# CharlieReactorBreakout.net
KiCad netlist of a schematic drawn in EAGLE
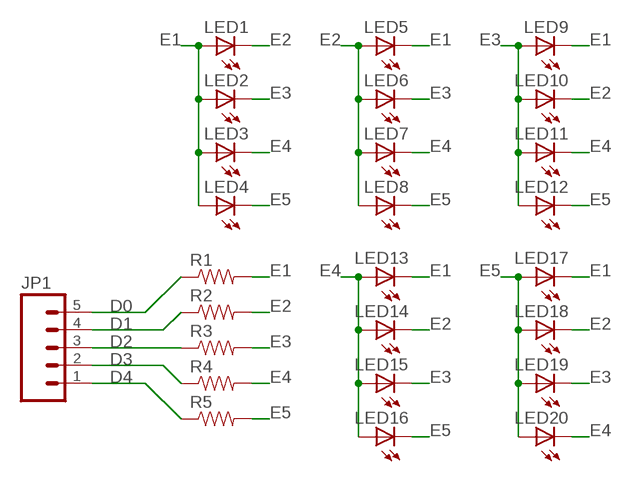
[diagram p0: schematic, sheet 1]

(export (version "E")
  (design (tool "Eeschema 10.0.6"))
  (components
    (comp (ref "JP1")
      (value "M05PTH")
      (footprint "eagle-import:1X05")
      (libsource (lib "eagle-import") (part "M05PTH"))
    )
    (comp (ref "LED1")
      (value "LEDOVAL")
      (footprint "eagle-import:LED-OVAL")
      (libsource (lib "eagle-import") (part "LEDOVAL"))
    )
    (comp (ref "LED2")
      (value "LEDOVAL")
      (footprint "eagle-import:LED-OVAL")
      (libsource (lib "eagle-import") (part "LEDOVAL"))
    )
    (comp (ref "LED3")
      (value "LEDOVAL")
      (footprint "eagle-import:LED-OVAL")
      (libsource (lib "eagle-import") (part "LEDOVAL"))
    )
    (comp (ref "LED4")
      (value "LEDOVAL")
      (footprint "eagle-import:LED-OVAL")
      (libsource (lib "eagle-import") (part "LEDOVAL"))
    )
    (comp (ref "LED5")
      (value "LEDOVAL")
      (footprint "eagle-import:LED-OVAL")
      (libsource (lib "eagle-import") (part "LEDOVAL"))
    )
    (comp (ref "LED6")
      (value "LEDOVAL")
      (footprint "eagle-import:LED-OVAL")
      (libsource (lib "eagle-import") (part "LEDOVAL"))
    )
    (comp (ref "LED7")
      (value "LEDOVAL")
      (footprint "eagle-import:LED-OVAL")
      (libsource (lib "eagle-import") (part "LEDOVAL"))
    )
    (comp (ref "LED8")
      (value "LEDOVAL")
      (footprint "eagle-import:LED-OVAL")
      (libsource (lib "eagle-import") (part "LEDOVAL"))
    )
    (comp (ref "LED9")
      (value "LEDOVAL")
      (footprint "eagle-import:LED-OVAL")
      (libsource (lib "eagle-import") (part "LEDOVAL"))
    )
    (comp (ref "LED10")
      (value "LEDOVAL")
      (footprint "eagle-import:LED-OVAL")
      (libsource (lib "eagle-import") (part "LEDOVAL"))
    )
    (comp (ref "LED11")
      (value "LEDOVAL")
      (footprint "eagle-import:LED-OVAL")
      (libsource (lib "eagle-import") (part "LEDOVAL"))
    )
    (comp (ref "LED12")
      (value "LEDOVAL")
      (footprint "eagle-import:LED-OVAL")
      (libsource (lib "eagle-import") (part "LEDOVAL"))
    )
    (comp (ref "LED13")
      (value "LEDOVAL")
      (footprint "eagle-import:LED-OVAL")
      (libsource (lib "eagle-import") (part "LEDOVAL"))
    )
    (comp (ref "LED14")
      (value "LEDOVAL")
      (footprint "eagle-import:LED-OVAL")
      (libsource (lib "eagle-import") (part "LEDOVAL"))
    )
    (comp (ref "LED15")
      (value "LEDOVAL")
      (footprint "eagle-import:LED-OVAL")
      (libsource (lib "eagle-import") (part "LEDOVAL"))
    )
    (comp (ref "LED16")
      (value "LEDOVAL")
      (footprint "eagle-import:LED-OVAL")
      (libsource (lib "eagle-import") (part "LEDOVAL"))
    )
    (comp (ref "LED17")
      (value "LEDOVAL")
      (footprint "eagle-import:LED-OVAL")
      (libsource (lib "eagle-import") (part "LEDOVAL"))
    )
    (comp (ref "LED18")
      (value "LEDOVAL")
      (footprint "eagle-import:LED-OVAL")
      (libsource (lib "eagle-import") (part "LEDOVAL"))
    )
    (comp (ref "LED19")
      (value "LEDOVAL")
      (footprint "eagle-import:LED-OVAL")
      (libsource (lib "eagle-import") (part "LEDOVAL"))
    )
    (comp (ref "LED20")
      (value "LEDOVAL")
      (footprint "eagle-import:LED-OVAL")
      (libsource (lib "eagle-import") (part "LEDOVAL"))
    )
    (comp (ref "R1")
      (value "RESISTORAXIAL-0.3")
      (footprint "eagle-import:AXIAL-0.3")
      (libsource (lib "eagle-import") (part "RESISTORAXIAL-0.3"))
    )
    (comp (ref "R2")
      (value "RESISTORAXIAL-0.3")
      (footprint "eagle-import:AXIAL-0.3")
      (libsource (lib "eagle-import") (part "RESISTORAXIAL-0.3"))
    )
    (comp (ref "R3")
      (value "RESISTORAXIAL-0.3")
      (footprint "eagle-import:AXIAL-0.3")
      (libsource (lib "eagle-import") (part "RESISTORAXIAL-0.3"))
    )
    (comp (ref "R4")
      (value "RESISTORAXIAL-0.3")
      (footprint "eagle-import:AXIAL-0.3")
      (libsource (lib "eagle-import") (part "RESISTORAXIAL-0.3"))
    )
    (comp (ref "R5")
      (value "RESISTORAXIAL-0.3")
      (footprint "eagle-import:AXIAL-0.3")
      (libsource (lib "eagle-import") (part "RESISTORAXIAL-0.3"))
    )
  )
  (nets
    (net (code "1") (name "/D0") (class "Default")
      (node (ref "JP1") (pin "5") (pinfunction "5_5") (pintype "passive"))
      (node (ref "R1") (pin "P$1") (pinfunction "1_P$1") (pintype "passive"))
    )
    (net (code "2") (name "/D1") (class "Default")
      (node (ref "JP1") (pin "4") (pinfunction "4_4") (pintype "passive"))
      (node (ref "R2") (pin "P$1") (pinfunction "1_P$1") (pintype "passive"))
    )
    (net (code "3") (name "/D2") (class "Default")
      (node (ref "JP1") (pin "3") (pinfunction "3_3") (pintype "passive"))
      (node (ref "R3") (pin "P$1") (pinfunction "1_P$1") (pintype "passive"))
    )
    (net (code "4") (name "/D3") (class "Default")
      (node (ref "JP1") (pin "2") (pinfunction "2_2") (pintype "passive"))
      (node (ref "R4") (pin "P$1") (pinfunction "1_P$1") (pintype "passive"))
    )
    (net (code "5") (name "/D4") (class "Default")
      (node (ref "JP1") (pin "1") (pinfunction "1_1") (pintype "passive"))
      (node (ref "R5") (pin "P$1") (pinfunction "1_P$1") (pintype "passive"))
    )
    (net (code "6") (name "/E1") (class "Default")
      (node (ref "LED1") (pin "ANODE") (pinfunction "A_ANODE") (pintype "passive"))
      (node (ref "LED13") (pin "CATHODE") (pinfunction "C_CATHODE") (pintype "passive"))
      (node (ref "LED17") (pin "CATHODE") (pinfunction "C_CATHODE") (pintype "passive"))
      (node (ref "LED2") (pin "ANODE") (pinfunction "A_ANODE") (pintype "passive"))
      (node (ref "LED3") (pin "ANODE") (pinfunction "A_ANODE") (pintype "passive"))
      (node (ref "LED4") (pin "ANODE") (pinfunction "A_ANODE") (pintype "passive"))
      (node (ref "LED5") (pin "CATHODE") (pinfunction "C_CATHODE") (pintype "passive"))
      (node (ref "LED9") (pin "CATHODE") (pinfunction "C_CATHODE") (pintype "passive"))
      (node (ref "R1") (pin "P$2") (pinfunction "2_P$2") (pintype "passive"))
    )
    (net (code "7") (name "/E2") (class "Default")
      (node (ref "LED1") (pin "CATHODE") (pinfunction "C_CATHODE") (pintype "passive"))
      (node (ref "LED10") (pin "CATHODE") (pinfunction "C_CATHODE") (pintype "passive"))
      (node (ref "LED14") (pin "CATHODE") (pinfunction "C_CATHODE") (pintype "passive"))
      (node (ref "LED18") (pin "CATHODE") (pinfunction "C_CATHODE") (pintype "passive"))
      (node (ref "LED5") (pin "ANODE") (pinfunction "A_ANODE") (pintype "passive"))
      (node (ref "LED6") (pin "ANODE") (pinfunction "A_ANODE") (pintype "passive"))
      (node (ref "LED7") (pin "ANODE") (pinfunction "A_ANODE") (pintype "passive"))
      (node (ref "LED8") (pin "ANODE") (pinfunction "A_ANODE") (pintype "passive"))
      (node (ref "R2") (pin "P$2") (pinfunction "2_P$2") (pintype "passive"))
    )
    (net (code "8") (name "/E3") (class "Default")
      (node (ref "LED10") (pin "ANODE") (pinfunction "A_ANODE") (pintype "passive"))
      (node (ref "LED11") (pin "ANODE") (pinfunction "A_ANODE") (pintype "passive"))
      (node (ref "LED12") (pin "ANODE") (pinfunction "A_ANODE") (pintype "passive"))
      (node (ref "LED15") (pin "CATHODE") (pinfunction "C_CATHODE") (pintype "passive"))
      (node (ref "LED19") (pin "CATHODE") (pinfunction "C_CATHODE") (pintype "passive"))
      (node (ref "LED2") (pin "CATHODE") (pinfunction "C_CATHODE") (pintype "passive"))
      (node (ref "LED6") (pin "CATHODE") (pinfunction "C_CATHODE") (pintype "passive"))
      (node (ref "LED9") (pin "ANODE") (pinfunction "A_ANODE") (pintype "passive"))
      (node (ref "R3") (pin "P$2") (pinfunction "2_P$2") (pintype "passive"))
    )
    (net (code "9") (name "/E4") (class "Default")
      (node (ref "LED11") (pin "CATHODE") (pinfunction "C_CATHODE") (pintype "passive"))
      (node (ref "LED13") (pin "ANODE") (pinfunction "A_ANODE") (pintype "passive"))
      (node (ref "LED14") (pin "ANODE") (pinfunction "A_ANODE") (pintype "passive"))
      (node (ref "LED15") (pin "ANODE") (pinfunction "A_ANODE") (pintype "passive"))
      (node (ref "LED16") (pin "ANODE") (pinfunction "A_ANODE") (pintype "passive"))
      (node (ref "LED20") (pin "CATHODE") (pinfunction "C_CATHODE") (pintype "passive"))
      (node (ref "LED3") (pin "CATHODE") (pinfunction "C_CATHODE") (pintype "passive"))
      (node (ref "LED7") (pin "CATHODE") (pinfunction "C_CATHODE") (pintype "passive"))
      (node (ref "R4") (pin "P$2") (pinfunction "2_P$2") (pintype "passive"))
    )
    (net (code "10") (name "/E5") (class "Default")
      (node (ref "LED12") (pin "CATHODE") (pinfunction "C_CATHODE") (pintype "passive"))
      (node (ref "LED16") (pin "CATHODE") (pinfunction "C_CATHODE") (pintype "passive"))
      (node (ref "LED17") (pin "ANODE") (pinfunction "A_ANODE") (pintype "passive"))
      (node (ref "LED18") (pin "ANODE") (pinfunction "A_ANODE") (pintype "passive"))
      (node (ref "LED19") (pin "ANODE") (pinfunction "A_ANODE") (pintype "passive"))
      (node (ref "LED20") (pin "ANODE") (pinfunction "A_ANODE") (pintype "passive"))
      (node (ref "LED4") (pin "CATHODE") (pinfunction "C_CATHODE") (pintype "passive"))
      (node (ref "LED8") (pin "CATHODE") (pinfunction "C_CATHODE") (pintype "passive"))
      (node (ref "R5") (pin "P$2") (pinfunction "2_P$2") (pintype "passive"))
    )
  )
)
